# tinyFan.net
KiCad netlist of a schematic drawn in Altium Designer
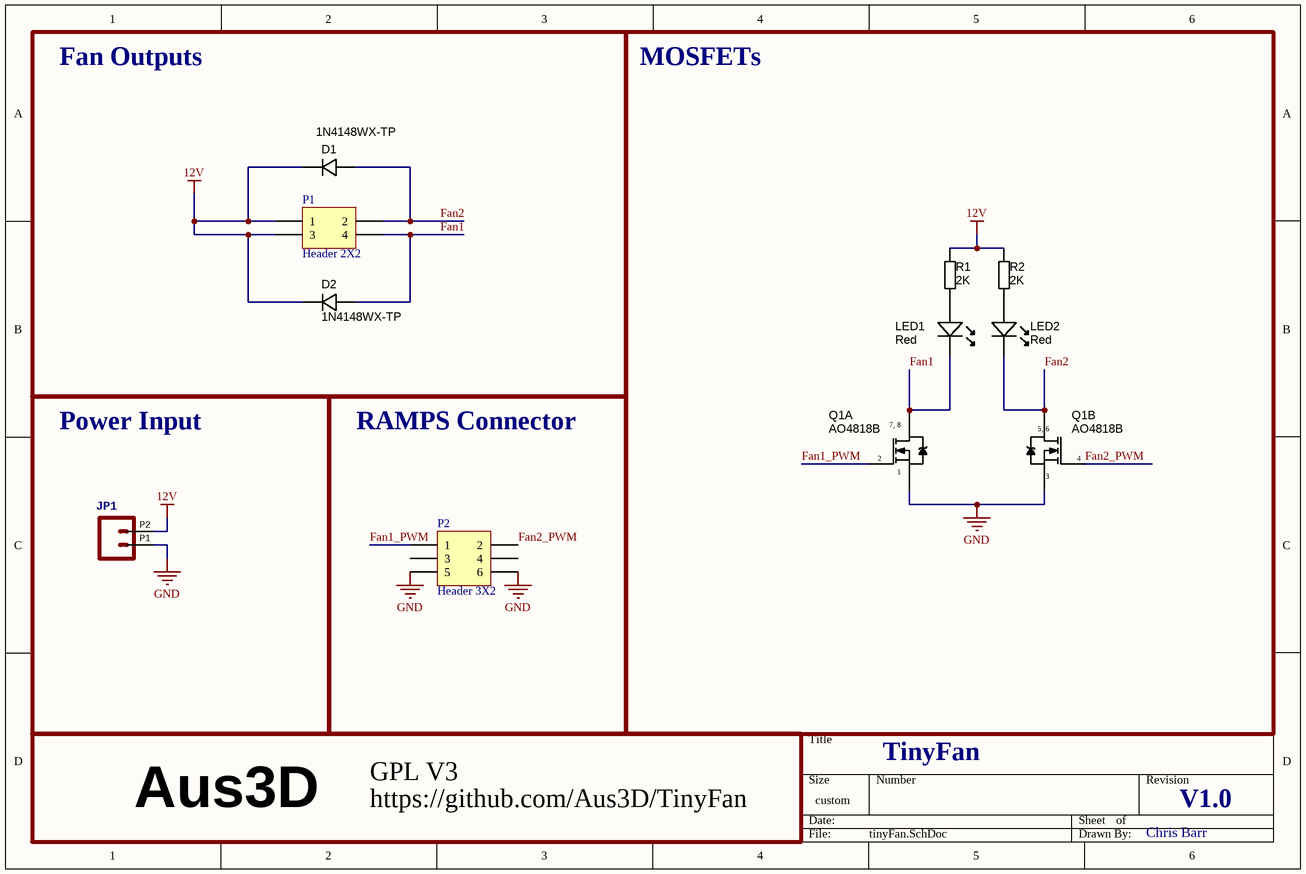
[diagram p0: tinyFan.SchDoc]

(export (version "E")
  (design (tool "Eeschema 10.0.6"))
  (components
    (comp (ref "D1")
      (value "DIODE_75V_500mW")
      (footprint "SOD323")
      (description "Diode SMD 300mA 0.5W SOD323")
      (fields
        (field (name "MANUFACTURER") "Micro Commercial Co")
        (field (name "MANUFACTURER PART NUMBER") "1N4148WX-TP")
      )
      (libsource (lib "PBL - Diodes") (part "DIODE_75V_500mW"))
    )
    (comp (ref "D2")
      (value "DIODE_75V_500mW")
      (footprint "SOD323")
      (description "Diode SMD 300mA 0.5W SOD323")
      (fields
        (field (name "MANUFACTURER") "Micro Commercial Co")
        (field (name "MANUFACTURER PART NUMBER") "1N4148WX-TP")
      )
      (libsource (lib "PBL - Diodes") (part "DIODE_75V_500mW"))
    )
    (comp (ref "JP1")
      (value "Standard 2-pin 0.1\" header. Use with  - straight break away headers ( PRT-00116) - right angle break away headers (PRT-00553) - swiss pins (PRT-00743) - machine pins (PRT-00117) - female headers (PRT-00115)   Molex polarized connector foot print use with: PRT-08233 with associated crimp pins and housings.  2.54_SCREWTERM for use with  PRT-10571.  3.5mm Screw Terminal footprints for  PRT-08084  5mm Screw Terminal footprints for use with PRT-08432")
      (footprint "1X02_2.54_SCREWTERM")
      (libsource (lib "SparkFun-Connectors") (part "M022.54MM_SCREWTERM"))
    )
    (comp (ref "LED1")
      (value "Red")
      (footprint "LED-0603-RED")
      (description "LED 0603 SMD Hyper Red 630nm 220mcd 20mA")
      (libsource (lib "PBL - Light Sources") (part "LED_SMD_Red_0603_220mcd"))
    )
    (comp (ref "LED2")
      (value "Red")
      (footprint "LED-0603-RED")
      (description "LED 0603 SMD Hyper Red 630nm 220mcd 20mA")
      (libsource (lib "PBL - Light Sources") (part "LED_SMD_Red_0603_220mcd"))
    )
    (comp (ref "P1")
      (value "Header 2X2")
      (footprint "Header-2x2-male")
      (description "Header, 2-Pin, Dual row")
      (fields (field (name "PUBLISHER") "Altium Limited"))
      (libsource (lib "Miscellaneous Connectors") (part "Header 2X2"))
    )
    (comp (ref "P2")
      (value "Header 3X2")
      (footprint "Header-3x2-female")
      (description "Header, 3-Pin, Dual row")
      (fields (field (name "PUBLISHER") "Altium Limited"))
      (libsource (lib "Miscellaneous Connectors") (part "Header 3X2"))
    )
    (comp (ref "Q1")
      (value "MOSFET_AO4818B")
      (footprint "SOIC127P600X175-8AN")
      (description "MOSFET Dual-Channel 30V 8.5A SOIC-8 SMD")
      (fields (field (name "MANUFACTURER PART NUMBER 1") "AO4818B"))
      (libsource (lib "PBL - Transistors") (part "MOSFET_AO4818B"))
    )
    (comp (ref "R1")
      (value "2K")
      (footprint "RESC1608X55N")
      (description "Resistor SMD chip 330 Ohm 0.1W 5% 0603")
      (fields (field (name "TOLERANCE") "±5%") (field (name "Comment") "Thick Film"))
      (libsource (lib "PBL - Resistors") (part "RES_330R_0603_5%"))
    )
    (comp (ref "R2")
      (value "2K")
      (footprint "RESC1608X55N")
      (description "Resistor SMD chip 330 Ohm 0.1W 5% 0603")
      (fields (field (name "TOLERANCE") "±5%") (field (name "Comment") "Thick Film"))
      (libsource (lib "PBL - Resistors") (part "RES_330R_0603_5%"))
    )
  )
  (nets
    (net (code "1") (name "/Fan1") (class "Default")
      (node (ref "D2") (pin "A") (pinfunction "A_A") (pintype "passive"))
      (node (ref "LED1") (pin "K") (pinfunction "K_K") (pintype "passive"))
      (node (ref "P1") (pin "4") (pinfunction "4_4") (pintype "passive"))
      (node (ref "Q1") (pin "7") (pinfunction "D_7") (pintype "passive"))
      (node (ref "Q1") (pin "8") (pinfunction "D_8") (pintype "passive"))
    )
    (net (code "2") (name "/Fan1_PWM") (class "Default")
      (node (ref "P2") (pin "1") (pinfunction "1_1") (pintype "passive"))
      (node (ref "Q1") (pin "2") (pinfunction "G_2") (pintype "passive"))
    )
    (net (code "3") (name "/Fan2") (class "Default")
      (node (ref "D1") (pin "A") (pinfunction "A_A") (pintype "passive"))
      (node (ref "LED2") (pin "K") (pinfunction "K_K") (pintype "passive"))
      (node (ref "P1") (pin "2") (pinfunction "2_2") (pintype "passive"))
      (node (ref "Q1") (pin "5") (pinfunction "D_5") (pintype "passive"))
      (node (ref "Q1") (pin "6") (pinfunction "D_6") (pintype "passive"))
    )
    (net (code "4") (name "/Fan2_PWM") (class "Default")
      (node (ref "P2") (pin "2") (pinfunction "2_2") (pintype "passive"))
      (node (ref "Q1") (pin "4") (pinfunction "G_4") (pintype "passive"))
    )
    (net (code "5") (name "12V") (class "Default")
      (node (ref "D1") (pin "K") (pinfunction "K_K") (pintype "passive"))
      (node (ref "D2") (pin "K") (pinfunction "K_K") (pintype "passive"))
      (node (ref "JP1") (pin "P2") (pinfunction "2_P2") (pintype "passive"))
      (node (ref "P1") (pin "1") (pinfunction "1_1") (pintype "passive"))
      (node (ref "P1") (pin "3") (pinfunction "3_3") (pintype "passive"))
      (node (ref "R1") (pin "1") (pinfunction "1_1") (pintype "passive"))
      (node (ref "R2") (pin "1") (pinfunction "1_1") (pintype "passive"))
    )
    (net (code "6") (name "GND") (class "Default")
      (node (ref "JP1") (pin "P1") (pinfunction "1_P1") (pintype "passive"))
      (node (ref "P2") (pin "5") (pinfunction "5_5") (pintype "passive"))
      (node (ref "P2") (pin "6") (pinfunction "6_6") (pintype "passive"))
      (node (ref "Q1") (pin "1") (pinfunction "S_1") (pintype "passive"))
      (node (ref "Q1") (pin "3") (pinfunction "S_3") (pintype "passive"))
    )
    (net (code "7") (name "Net-(LED1-PadA)") (class "Default")
      (node (ref "LED1") (pin "A") (pinfunction "A_A") (pintype "passive"))
      (node (ref "R1") (pin "2") (pinfunction "2_2") (pintype "passive"))
    )
    (net (code "8") (name "Net-(LED2-PadA)") (class "Default")
      (node (ref "LED2") (pin "A") (pinfunction "A_A") (pintype "passive"))
      (node (ref "R2") (pin "2") (pinfunction "2_2") (pintype "passive"))
    )
    (net (code "9") (name "unconnected-(P2-Pad3)") (class "Default")
      (node (ref "P2") (pin "3") (pinfunction "3_3") (pintype "passive"))
    )
    (net (code "10") (name "unconnected-(P2-Pad4)") (class "Default")
      (node (ref "P2") (pin "4") (pinfunction "4_4") (pintype "passive"))
    )
  )
)
